# untitled.net
KiCad netlist of a schematic drawn in EAGLE
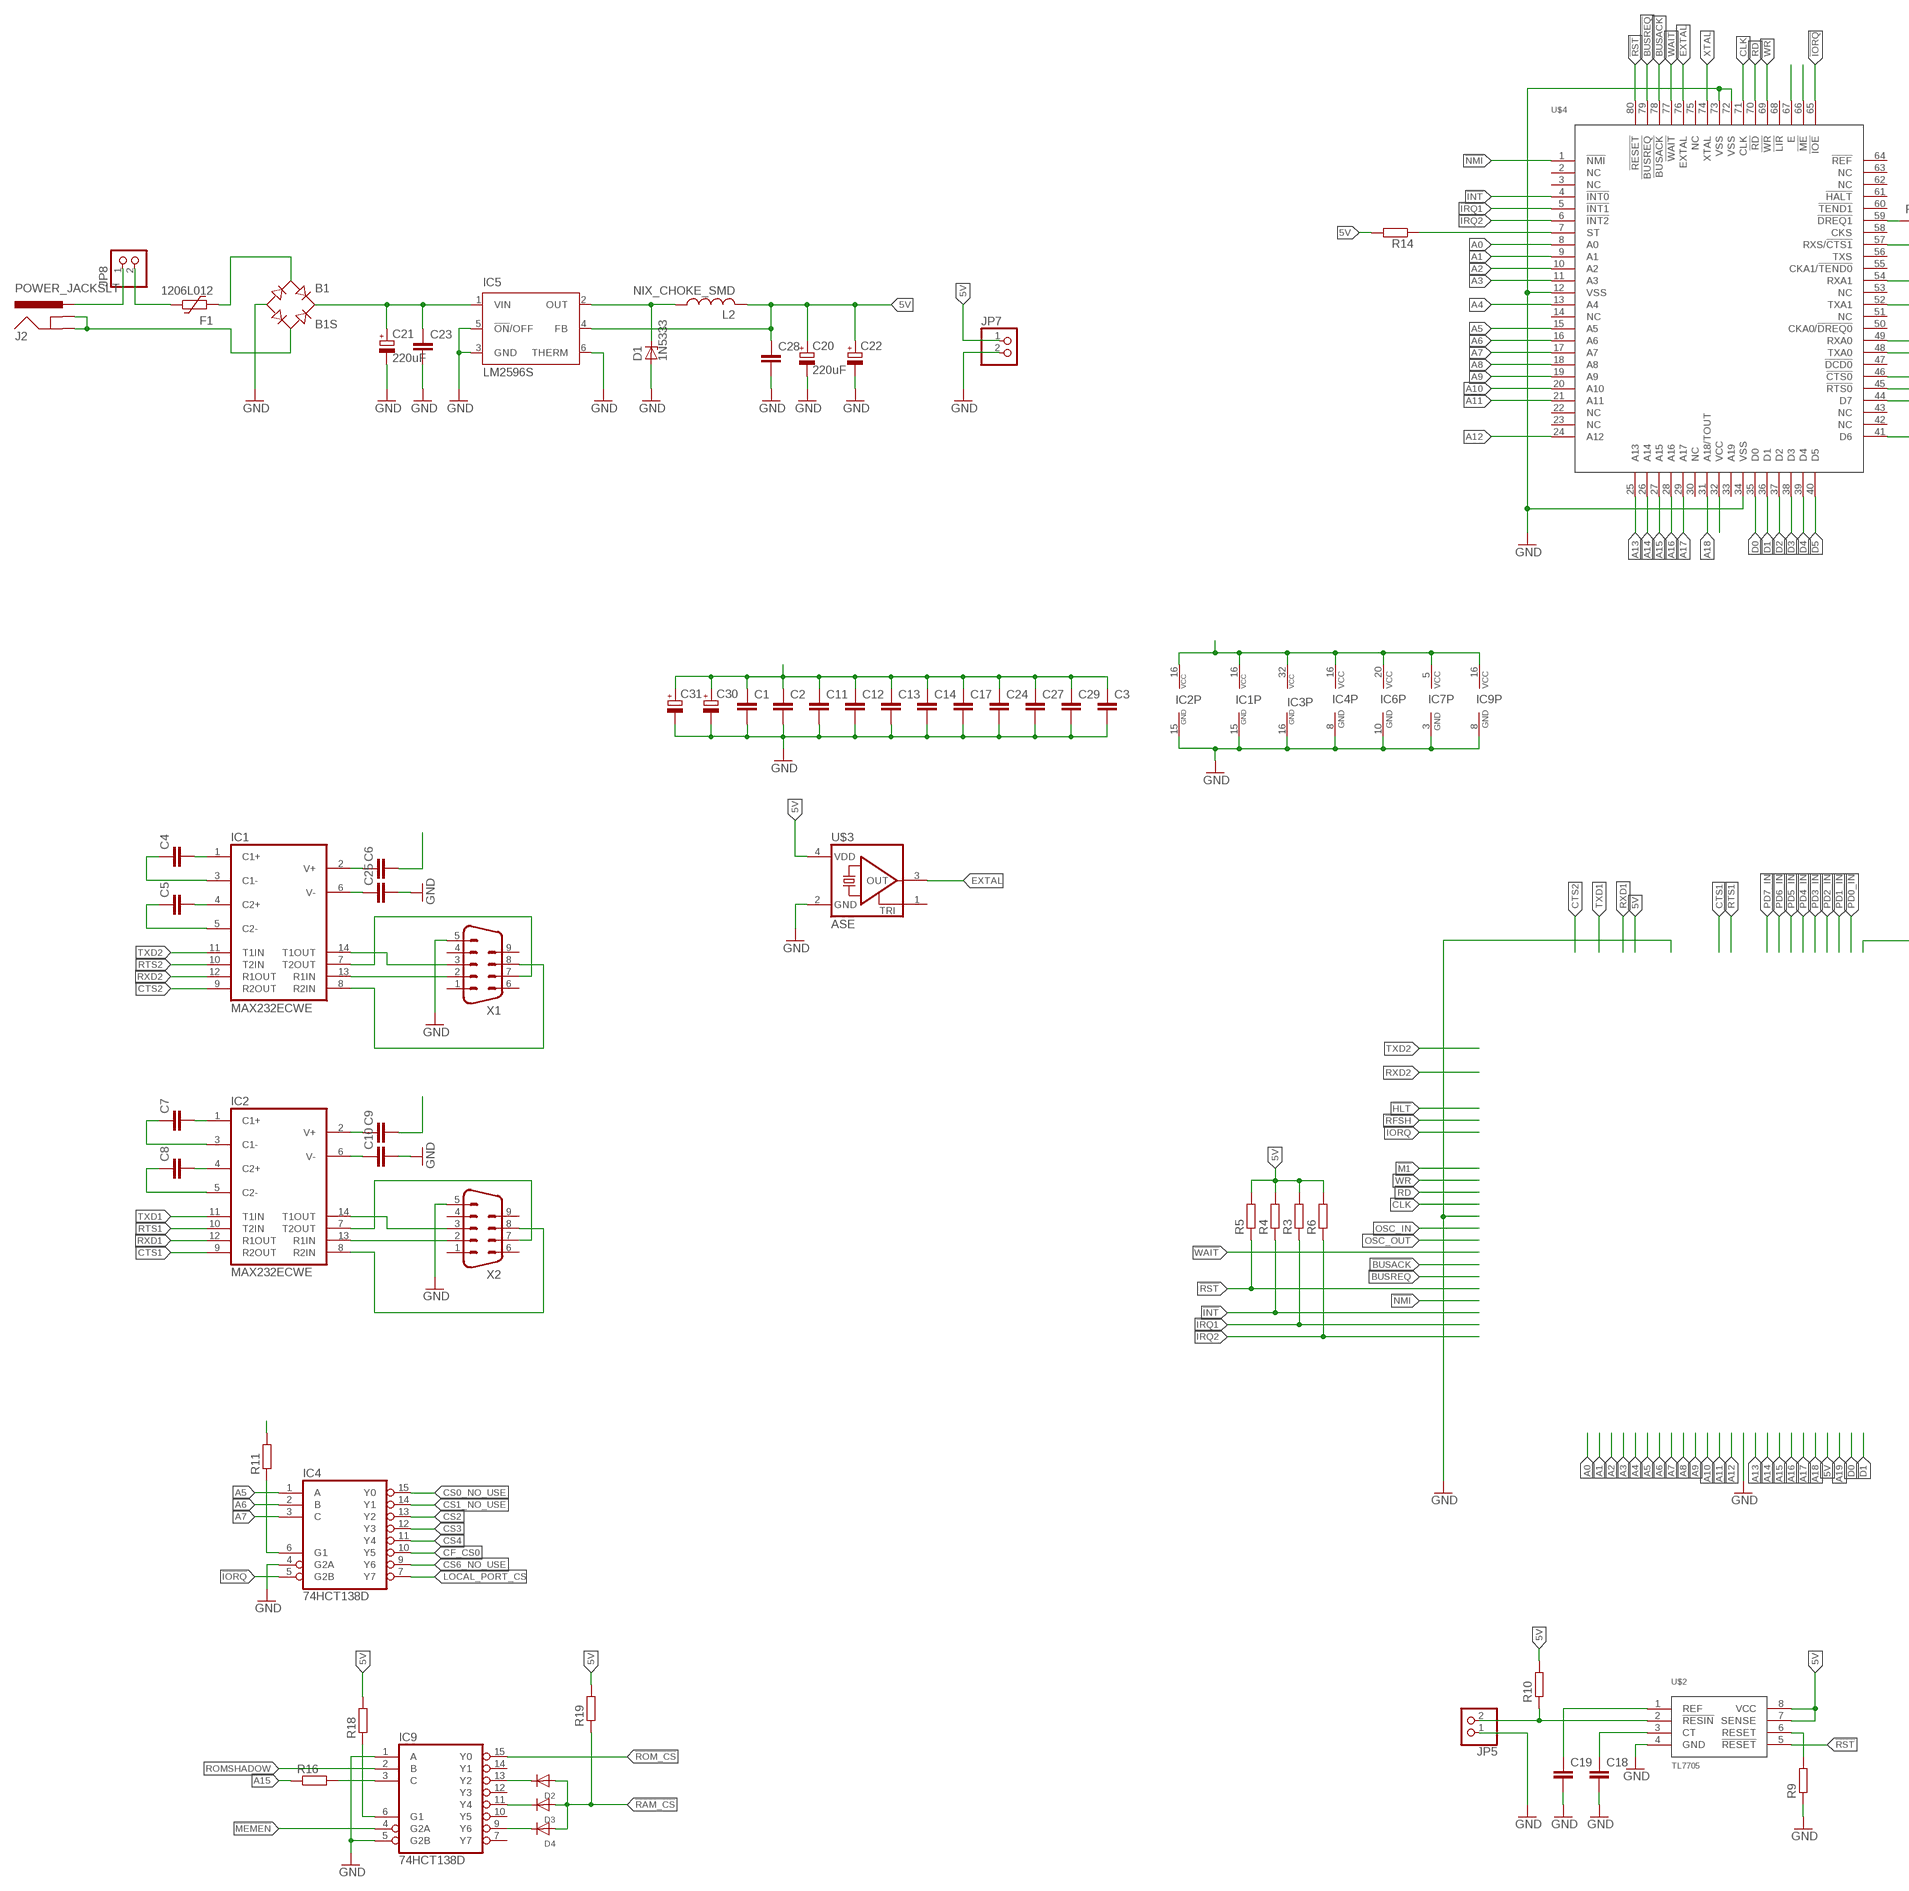
[diagram p0: schematic, sheet 1, part 1 of 2]
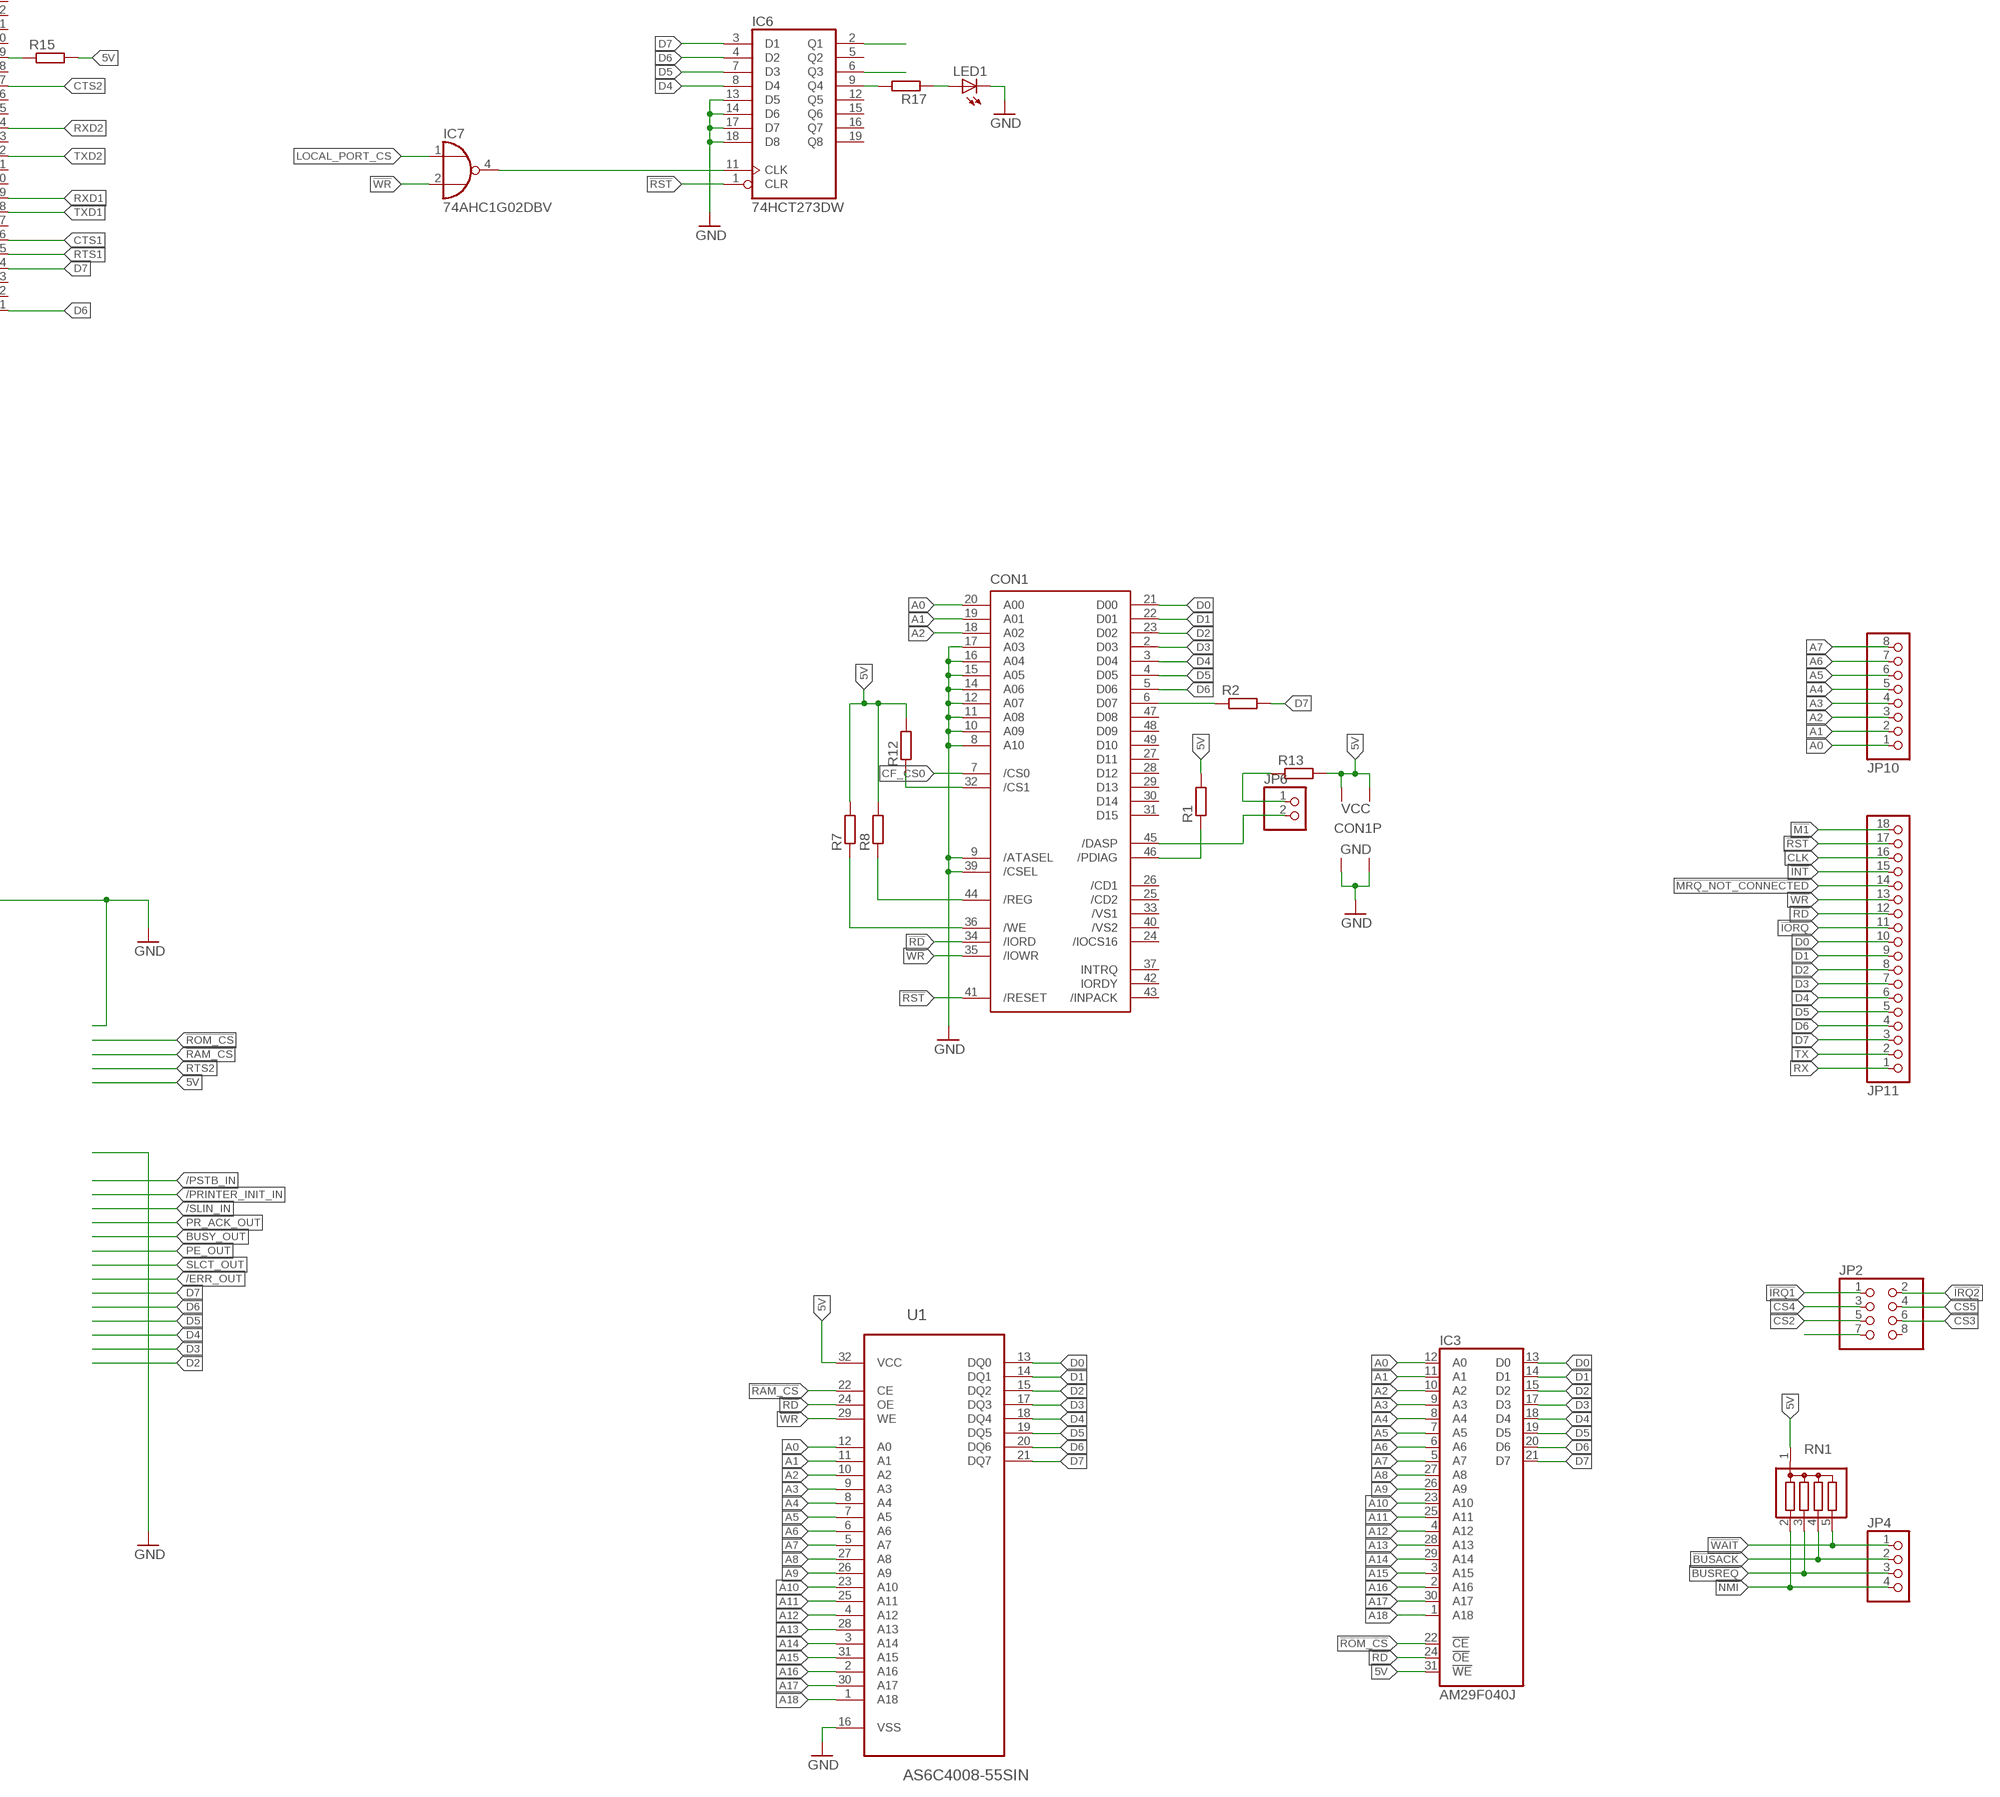
[diagram p1: schematic, sheet 1, part 2 of 2]

(export (version "E")
  (design (tool "Eeschema 10.0.6"))
  (components
    (comp (ref "B1")
      (value "B1S")
      (footprint "eagle-import:MBS")
      (libsource (lib "eagle-import") (part "BS1"))
    )
    (comp (ref "C1")
      (value "C-EUC0603")
      (footprint "eagle-import:C0603")
      (libsource (lib "eagle-import") (part "C-EUC0603"))
    )
    (comp (ref "C2")
      (value "C-EUC0603")
      (footprint "eagle-import:C0603")
      (libsource (lib "eagle-import") (part "C-EUC0603"))
    )
    (comp (ref "C3")
      (value "C-EUC0603")
      (footprint "eagle-import:C0603")
      (libsource (lib "eagle-import") (part "C-EUC0603"))
    )
    (comp (ref "C4")
      (value "C-EUC0603")
      (footprint "eagle-import:C0603")
      (libsource (lib "eagle-import") (part "C-EUC0603"))
    )
    (comp (ref "C5")
      (value "C-EUC0603")
      (footprint "eagle-import:C0603")
      (libsource (lib "eagle-import") (part "C-EUC0603"))
    )
    (comp (ref "C6")
      (value "C-EUC0603")
      (footprint "eagle-import:C0603")
      (libsource (lib "eagle-import") (part "C-EUC0603"))
    )
    (comp (ref "C7")
      (value "C-EUC0603")
      (footprint "eagle-import:C0603")
      (libsource (lib "eagle-import") (part "C-EUC0603"))
    )
    (comp (ref "C8")
      (value "C-EUC0603")
      (footprint "eagle-import:C0603")
      (libsource (lib "eagle-import") (part "C-EUC0603"))
    )
    (comp (ref "C9")
      (value "C-EUC0603")
      (footprint "eagle-import:C0603")
      (libsource (lib "eagle-import") (part "C-EUC0603"))
    )
    (comp (ref "C10")
      (value "C-EUC0603")
      (footprint "eagle-import:C0603")
      (libsource (lib "eagle-import") (part "C-EUC0603"))
    )
    (comp (ref "C11")
      (value "C-EUC0603")
      (footprint "eagle-import:C0603")
      (libsource (lib "eagle-import") (part "C-EUC0603"))
    )
    (comp (ref "C12")
      (value "C-EUC0603")
      (footprint "eagle-import:C0603")
      (libsource (lib "eagle-import") (part "C-EUC0603"))
    )
    (comp (ref "C13")
      (value "C-EUC0402")
      (footprint "eagle-import:C0402")
      (libsource (lib "eagle-import") (part "C-EUC0402"))
    )
    (comp (ref "C14")
      (value "C-EUC0603")
      (footprint "eagle-import:C0603")
      (libsource (lib "eagle-import") (part "C-EUC0603"))
    )
    (comp (ref "C17")
      (value "C-EUC0603")
      (footprint "eagle-import:C0603")
      (libsource (lib "eagle-import") (part "C-EUC0603"))
    )
    (comp (ref "C18")
      (value "C-EUC0603")
      (footprint "eagle-import:C0603")
      (libsource (lib "eagle-import") (part "C-EUC0603"))
    )
    (comp (ref "C19")
      (value "C-EUC0603")
      (footprint "eagle-import:C0603")
      (libsource (lib "eagle-import") (part "C-EUC0603"))
    )
    (comp (ref "C20")
      (value "220uF")
      (footprint "eagle-import:153CLV-0810")
      (libsource (lib "eagle-import") (part "CPOL-EU153CLV-0810"))
    )
    (comp (ref "C21")
      (value "220uF")
      (footprint "eagle-import:153CLV-0810")
      (libsource (lib "eagle-import") (part "CPOL-EU153CLV-0810"))
    )
    (comp (ref "C22")
      (value "CPOL-EUSMCC")
      (footprint "eagle-import:SMC_C")
      (libsource (lib "eagle-import") (part "CPOL-EUSMCC"))
    )
    (comp (ref "C23")
      (value "C-EUC0603")
      (footprint "eagle-import:C0603")
      (libsource (lib "eagle-import") (part "C-EUC0603"))
    )
    (comp (ref "C24")
      (value "C-EUC0603")
      (footprint "eagle-import:C0603")
      (libsource (lib "eagle-import") (part "C-EUC0603"))
    )
    (comp (ref "C25")
      (value "C-EUC0603")
      (footprint "eagle-import:C0603")
      (libsource (lib "eagle-import") (part "C-EUC0603"))
    )
    (comp (ref "C27")
      (value "C-EUC0603")
      (footprint "eagle-import:C0603")
      (libsource (lib "eagle-import") (part "C-EUC0603"))
    )
    (comp (ref "C28")
      (value "C-EUC0603")
      (footprint "eagle-import:C0603")
      (libsource (lib "eagle-import") (part "C-EUC0603"))
    )
    (comp (ref "C29")
      (value "C-EUC0603")
      (footprint "eagle-import:C0603")
      (libsource (lib "eagle-import") (part "C-EUC0603"))
    )
    (comp (ref "C30")
      (value "CPOL-EUSMCB")
      (footprint "eagle-import:SMC_B")
      (libsource (lib "eagle-import") (part "CPOL-EUSMCB"))
    )
    (comp (ref "C31")
      (value "CPOL-EUSMCB")
      (footprint "eagle-import:SMC_B")
      (libsource (lib "eagle-import") (part "CPOL-EUSMCB"))
    )
    (comp (ref "CON1")
      (value "CF-CARD-IDE_MODE")
      (footprint "eagle-import:MI20-50PD-SF")
      (libsource (lib "eagle-import") (part "CF-CARD-IDE_MODE"))
    )
    (comp (ref "D1")
      (value "1N5333")
      (footprint "eagle-import:C1702-15")
      (libsource (lib "eagle-import") (part "1N5333"))
    )
    (comp (ref "D2")
      (value "DIODESOD-323")
      (footprint "eagle-import:SOD-323")
      (libsource (lib "eagle-import") (part "DIODESOD-323"))
    )
    (comp (ref "D3")
      (value "DIODESOD-323")
      (footprint "eagle-import:SOD-323")
      (libsource (lib "eagle-import") (part "DIODESOD-323"))
    )
    (comp (ref "D4")
      (value "DIODESOD-323")
      (footprint "eagle-import:SOD-323")
      (libsource (lib "eagle-import") (part "DIODESOD-323"))
    )
    (comp (ref "F1")
      (value "1206L012")
      (footprint "eagle-import:1206L")
      (fields (field (name "MF") "Littelfuse"))
      (libsource (lib "eagle-import") (part "?1206L012"))
    )
    (comp (ref "IC1")
      (value "MAX232ECWE")
      (footprint "eagle-import:SO16L")
      (fields (field (name "MF") "MAXIM") (field (name "MPN") "MAX232ECWE+"))
      (libsource (lib "eagle-import") (part "MAX232ECWE"))
    )
    (comp (ref "IC2")
      (value "MAX232ECWE")
      (footprint "eagle-import:SO16L")
      (fields (field (name "MF") "MAXIM") (field (name "MPN") "MAX232ECWE+"))
      (libsource (lib "eagle-import") (part "MAX232ECWE"))
    )
    (comp (ref "IC3")
      (value "AM29F040J")
      (footprint "eagle-import:PLCC32R")
      (libsource (lib "eagle-import") (part "AM29F040J"))
    )
    (comp (ref "IC4")
      (value "74HCT138D")
      (footprint "eagle-import:SO16")
      (libsource (lib "eagle-import") (part "74138DHCT"))
    )
    (comp (ref "IC5")
      (value "LM2596S")
      (footprint "eagle-import:TO263-5")
      (fields (field (name "MF") "NATIONAL SEMICONDUCTOR") (field (name "MPN") "LM2596S-ADJ/NOPB"))
      (libsource (lib "eagle-import") (part "LM2596S"))
    )
    (comp (ref "IC6")
      (value "74HCT273DW")
      (footprint "eagle-import:SO20W")
      (libsource (lib "eagle-import") (part "74273DWHCT"))
    )
    (comp (ref "IC7")
      (value "74AHC1G02DBV")
      (footprint "eagle-import:SOT23-5")
      (libsource (lib "eagle-import") (part "741G02DBVAHC"))
    )
    (comp (ref "IC9")
      (value "74HCT138D")
      (footprint "eagle-import:SO16")
      (libsource (lib "eagle-import") (part "74138DHCT"))
    )
    (comp (ref "J2")
      (value "POWER_JACKSLT")
      (footprint "eagle-import:POWER_JACK_SLOT")
      (libsource (lib "eagle-import") (part "POWER_JACKSLT"))
    )
    (comp (ref "JP2")
      (value "PINHD-2X4")
      (footprint "eagle-import:2X04")
      (libsource (lib "eagle-import") (part "PINHD-2X4"))
    )
    (comp (ref "JP4")
      (value "PINHD-1X4")
      (footprint "eagle-import:1X04")
      (libsource (lib "eagle-import") (part "PINHD-1X4"))
    )
    (comp (ref "JP5")
      (value "PINHD-1X2")
      (footprint "eagle-import:1X02")
      (libsource (lib "eagle-import") (part "PINHD-1X2"))
    )
    (comp (ref "JP6")
      (value "PINHD-1X2")
      (footprint "eagle-import:1X02")
      (libsource (lib "eagle-import") (part "PINHD-1X2"))
    )
    (comp (ref "JP7")
      (value "PINHD-1X2")
      (footprint "eagle-import:1X02")
      (libsource (lib "eagle-import") (part "PINHD-1X2"))
    )
    (comp (ref "JP8")
      (value "PINHD-1X2")
      (footprint "eagle-import:1X02")
      (libsource (lib "eagle-import") (part "PINHD-1X2"))
    )
    (comp (ref "JP10")
      (value "PINHD-1X8")
      (footprint "eagle-import:1X08")
      (libsource (lib "eagle-import") (part "PINHD-1X8"))
    )
    (comp (ref "JP11")
      (value "PINHD-1X18")
      (footprint "eagle-import:1X18")
      (libsource (lib "eagle-import") (part "PINHD-1X18"))
    )
    (comp (ref "L2")
      (value "NIX_CHOKE_SMD")
      (footprint "eagle-import:NIX_CHOKE_SMD")
      (libsource (lib "eagle-import") (part "NIX_CHOKE_SMD"))
    )
    (comp (ref "LED1")
      (value "LEDCHIP-LED0603")
      (footprint "eagle-import:CHIP-LED0603")
      (libsource (lib "eagle-import") (part "LEDCHIP-LED0603"))
    )
    (comp (ref "R1")
      (value "R-EU_R0603")
      (footprint "eagle-import:R0603")
      (libsource (lib "eagle-import") (part "R-EU_R0603"))
    )
    (comp (ref "R2")
      (value "R-EU_R0603")
      (footprint "eagle-import:R0603")
      (libsource (lib "eagle-import") (part "R-EU_R0603"))
    )
    (comp (ref "R3")
      (value "R-EU_R0402")
      (footprint "eagle-import:R0402")
      (libsource (lib "eagle-import") (part "R-EU_R0402"))
    )
    (comp (ref "R4")
      (value "R-EU_R0402")
      (footprint "eagle-import:R0402")
      (libsource (lib "eagle-import") (part "R-EU_R0402"))
    )
    (comp (ref "R5")
      (value "R-EU_R1206")
      (footprint "eagle-import:R1206")
      (libsource (lib "eagle-import") (part "R-EU_R1206"))
    )
    (comp (ref "R6")
      (value "R-EU_R0402")
      (footprint "eagle-import:R0402")
      (libsource (lib "eagle-import") (part "R-EU_R0402"))
    )
    (comp (ref "R7")
      (value "R-EU_R0603")
      (footprint "eagle-import:R0603")
      (libsource (lib "eagle-import") (part "R-EU_R0603"))
    )
    (comp (ref "R8")
      (value "R-EU_R0603")
      (footprint "eagle-import:R0603")
      (libsource (lib "eagle-import") (part "R-EU_R0603"))
    )
    (comp (ref "R9")
      (value "R-EU_R0603")
      (footprint "eagle-import:R0603")
      (libsource (lib "eagle-import") (part "R-EU_R0603"))
    )
    (comp (ref "R10")
      (value "R-EU_M1206")
      (footprint "eagle-import:M1206")
      (libsource (lib "eagle-import") (part "R-EU_M1206"))
    )
    (comp (ref "R11")
      (value "R-EU_R0603")
      (footprint "eagle-import:R0603")
      (libsource (lib "eagle-import") (part "R-EU_R0603"))
    )
    (comp (ref "R12")
      (value "R-EU_R0603")
      (footprint "eagle-import:R0603")
      (libsource (lib "eagle-import") (part "R-EU_R0603"))
    )
    (comp (ref "R13")
      (value "R-EU_R0603")
      (footprint "eagle-import:R0603")
      (libsource (lib "eagle-import") (part "R-EU_R0603"))
    )
    (comp (ref "R14")
      (value "R-EU_0204/5")
      (footprint "eagle-import:0204_5")
      (libsource (lib "eagle-import") (part "R-EU_0204/5"))
    )
    (comp (ref "R15")
      (value "R-EU_R0603")
      (footprint "eagle-import:R0603")
      (libsource (lib "eagle-import") (part "R-EU_R0603"))
    )
    (comp (ref "R16")
      (value "R-EU_R0603")
      (footprint "eagle-import:R0603")
      (libsource (lib "eagle-import") (part "R-EU_R0603"))
    )
    (comp (ref "R17")
      (value "R-EU_R0603")
      (footprint "eagle-import:R0603")
      (libsource (lib "eagle-import") (part "R-EU_R0603"))
    )
    (comp (ref "R18")
      (value "R-EU_R0603")
      (footprint "eagle-import:R0603")
      (libsource (lib "eagle-import") (part "R-EU_R0603"))
    )
    (comp (ref "R19")
      (value "R-EU_R0603")
      (footprint "eagle-import:R0603")
      (libsource (lib "eagle-import") (part "R-EU_R0603"))
    )
    (comp (ref "RN1")
      (value "G04R")
      (footprint "eagle-import:SIL5")
      (libsource (lib "eagle-import") (part "G04R"))
    )
    (comp (ref "U$2")
      (value "TL7705")
      (footprint "eagle-import:SOIC8")
      (libsource (lib "eagle-import") (part "TL7705"))
    )
    (comp (ref "U$3")
      (value "ASE")
      (footprint "eagle-import:ASE")
      (libsource (lib "eagle-import") (part "ASE"))
    )
    (comp (ref "U$4")
      (value "HD64180QFP80_")
      (footprint "eagle-import:QFP80")
      (libsource (lib "eagle-import") (part "HD64180QFP80_"))
    )
    (comp (ref "U1")
      (value "AS6C4008-55SIN")
      (footprint "eagle-import:SOIC127P1407X299-32N")
      (libsource (lib "eagle-import") (part "AS6C4008-55SIN"))
    )
    (comp (ref "X1")
      (value "M09HP")
      (footprint "eagle-import:M09HP")
      (libsource (lib "eagle-import") (part "M09HP"))
    )
    (comp (ref "X2")
      (value "M09HP")
      (footprint "eagle-import:M09HP")
      (libsource (lib "eagle-import") (part "M09HP"))
    )
  )
  (nets
    (net (code "1") (name "/E") (class "Default")
      (node (ref "JP2") (pin "7") (pinfunction "7_7") (pintype "passive"))
      (node (ref "U$4") (pin "67") (pinfunction "E_67") (pintype "bidirectional"))
    )
    (net (code "2") (name "/~{BUSACK}") (class "Default")
      (node (ref "JP4") (pin "2") (pinfunction "2_2") (pintype "passive"))
      (node (ref "RN1") (pin "4") (pinfunction "4_4") (pintype "passive"))
      (node (ref "U$4") (pin "78") (pinfunction "~{BUSACK}_78") (pintype "bidirectional"))
    )
    (net (code "3") (name "/~{BUSREQ}") (class "Default")
      (node (ref "JP4") (pin "3") (pinfunction "3_3") (pintype "passive"))
      (node (ref "RN1") (pin "3") (pinfunction "3_3") (pintype "passive"))
      (node (ref "U$4") (pin "79") (pinfunction "~{BUSREQ}_79") (pintype "bidirectional"))
    )
    (net (code "5") (name "/~{INT}") (class "Default")
      (node (ref "JP11") (pin "15") (pinfunction "15_15") (pintype "passive"))
      (node (ref "R4") (pin "1") (pinfunction "1_1") (pintype "passive"))
      (node (ref "U$4") (pin "4") (pinfunction "~{INT0}_4") (pintype "bidirectional"))
    )
    (net (code "6") (name "/~{IORQ}") (class "Default")
      (node (ref "IC4") (pin "5") (pinfunction "G2B_5") (pintype "input"))
      (node (ref "JP11") (pin "11") (pinfunction "11_11") (pintype "passive"))
      (node (ref "U$4") (pin "65") (pinfunction "~{IOE}_65") (pintype "bidirectional"))
    )
    (net (code "7") (name "/~{IRQ1}") (class "Default")
      (node (ref "JP2") (pin "1") (pinfunction "1_1") (pintype "passive"))
      (node (ref "R3") (pin "1") (pinfunction "1_1") (pintype "passive"))
      (node (ref "U$4") (pin "5") (pinfunction "~{INT1}_5") (pintype "bidirectional"))
    )
    (net (code "8") (name "/~{IRQ2}") (class "Default")
      (node (ref "JP2") (pin "2") (pinfunction "2_2") (pintype "passive"))
      (node (ref "R6") (pin "1") (pinfunction "1_1") (pintype "passive"))
      (node (ref "U$4") (pin "6") (pinfunction "~{INT2}_6") (pintype "bidirectional"))
    )
    (net (code "9") (name "/~{M1}") (class "Default")
      (node (ref "JP11") (pin "18") (pinfunction "18_18") (pintype "passive"))
    )
    (net (code "10") (name "/~{MEMEN}") (class "Default")
      (node (ref "IC9") (pin "4") (pinfunction "G2A_4") (pintype "input"))
      (node (ref "U$4") (pin "66") (pinfunction "~{ME}_66") (pintype "bidirectional"))
    )
    (net (code "11") (name "/~{MRQ_NOT_CONNECTED}") (class "Default")
      (node (ref "JP11") (pin "14") (pinfunction "14_14") (pintype "passive"))
    )
    (net (code "12") (name "/~{NMI}") (class "Default")
      (node (ref "JP4") (pin "4") (pinfunction "4_4") (pintype "passive"))
      (node (ref "RN1") (pin "2") (pinfunction "2_2") (pintype "passive"))
      (node (ref "U$4") (pin "1") (pinfunction "~{NMI}_1") (pintype "bidirectional"))
    )
    (net (code "13") (name "/~{RAM_CS}") (class "Default")
      (node (ref "D2") (pin "A") (pinfunction "A_A") (pintype "passive"))
      (node (ref "D3") (pin "A") (pinfunction "A_A") (pintype "passive"))
      (node (ref "D4") (pin "A") (pinfunction "A_A") (pintype "passive"))
      (node (ref "R19") (pin "1") (pinfunction "1_1") (pintype "passive"))
      (node (ref "U1") (pin "22") (pinfunction "CE_22") (pintype "input"))
    )
    (net (code "14") (name "/~{RD}") (class "Default")
      (node (ref "CON1") (pin "34") (pinfunction "/IORD_34") (pintype "input"))
      (node (ref "IC3") (pin "24") (pinfunction "~{OE}_24") (pintype "input"))
      (node (ref "JP11") (pin "12") (pinfunction "12_12") (pintype "passive"))
      (node (ref "U$4") (pin "70") (pinfunction "~{RD}_70") (pintype "bidirectional"))
      (node (ref "U1") (pin "24") (pinfunction "OE_24") (pintype "input"))
    )
    (net (code "16") (name "/~{ROM_CS}") (class "Default")
      (node (ref "IC3") (pin "22") (pinfunction "~{CE}_22") (pintype "input"))
      (node (ref "IC9") (pin "15") (pinfunction "Y0_15") (pintype "output"))
    )
    (net (code "17") (name "/~{RST}") (class "Default")
      (node (ref "CON1") (pin "41") (pinfunction "/RESET_41") (pintype "input"))
      (node (ref "IC6") (pin "1") (pinfunction "CLR_1") (pintype "input"))
      (node (ref "JP11") (pin "17") (pinfunction "17_17") (pintype "passive"))
      (node (ref "R5") (pin "1") (pinfunction "1_1") (pintype "passive"))
      (node (ref "U$2") (pin "5") (pinfunction "~{RESET}_5") (pintype "bidirectional"))
      (node (ref "U$4") (pin "80") (pinfunction "~{RESET}_80") (pintype "bidirectional"))
    )
    (net (code "18") (name "/~{WAIT}") (class "Default")
      (node (ref "JP4") (pin "1") (pinfunction "1_1") (pintype "passive"))
      (node (ref "RN1") (pin "5") (pinfunction "5_5") (pintype "passive"))
      (node (ref "U$4") (pin "77") (pinfunction "~{WAIT}_77") (pintype "bidirectional"))
    )
    (net (code "19") (name "/~{WR}") (class "Default")
      (node (ref "CON1") (pin "35") (pinfunction "/IOWR_35") (pintype "input"))
      (node (ref "IC7") (pin "2") (pinfunction "I1_2") (pintype "input"))
      (node (ref "JP11") (pin "13") (pinfunction "13_13") (pintype "passive"))
      (node (ref "U$4") (pin "69") (pinfunction "~{WR}_69") (pintype "bidirectional"))
      (node (ref "U1") (pin "29") (pinfunction "WE_29") (pintype "input"))
    )
    (net (code "20") (name "5V") (class "Default")
      (node (ref "C1") (pin "1") (pinfunction "1_1") (pintype "passive"))
      (node (ref "C11") (pin "1") (pinfunction "1_1") (pintype "passive"))
      (node (ref "C12") (pin "1") (pinfunction "1_1") (pintype "passive"))
      (node (ref "C13") (pin "1") (pinfunction "1_1") (pintype "passive"))
      (node (ref "C14") (pin "1") (pinfunction "1_1") (pintype "passive"))
      (node (ref "C17") (pin "1") (pinfunction "1_1") (pintype "passive"))
      (node (ref "C2") (pin "1") (pinfunction "1_1") (pintype "passive"))
      (node (ref "C20") (pin "+") (pinfunction "+_+") (pintype "passive"))
      (node (ref "C22") (pin "+") (pinfunction "+_+") (pintype "passive"))
      (node (ref "C24") (pin "1") (pinfunction "1_1") (pintype "passive"))
      (node (ref "C27") (pin "1") (pinfunction "1_1") (pintype "passive"))
      (node (ref "C28") (pin "1") (pinfunction "1_1") (pintype "passive"))
      (node (ref "C29") (pin "1") (pinfunction "1_1") (pintype "passive"))
      (node (ref "C3") (pin "1") (pinfunction "1_1") (pintype "passive"))
      (node (ref "C30") (pin "+") (pinfunction "+_+") (pintype "passive"))
      (node (ref "C31") (pin "+") (pinfunction "+_+") (pintype "passive"))
      (node (ref "C6") (pin "2") (pinfunction "2_2") (pintype "passive"))
      (node (ref "C9") (pin "2") (pinfunction "2_2") (pintype "passive"))
      (node (ref "CON1") (pin "13") (pinfunction "VCC2_13") (pintype "power_in"))
      (node (ref "CON1") (pin "38") (pinfunction "VCC1_38") (pintype "power_in"))
      (node (ref "IC1") (pin "16") (pinfunction "VCC_16") (pintype "power_in"))
      (node (ref "IC2") (pin "16") (pinfunction "VCC_16") (pintype "power_in"))
      (node (ref "IC3") (pin "31") (pinfunction "~{WE}_31") (pintype "input"))
      (node (ref "IC3") (pin "32") (pinfunction "VCC_32") (pintype "power_in"))
      (node (ref "IC4") (pin "16") (pinfunction "VCC_16") (pintype "power_in"))
      (node (ref "IC5") (pin "4") (pinfunction "FB_4") (pintype "input"))
      (node (ref "IC6") (pin "20") (pinfunction "VCC_20") (pintype "power_in"))
      (node (ref "IC7") (pin "5") (pinfunction "VCC_5") (pintype "power_in"))
      (node (ref "IC9") (pin "16") (pinfunction "VCC_16") (pintype "power_in"))
      (node (ref "JP7") (pin "1") (pinfunction "1_1") (pintype "passive"))
      (node (ref "L2") (pin "P$2") (pinfunction "2_P$2") (pintype "passive"))
      (node (ref "R1") (pin "2") (pinfunction "2_2") (pintype "passive"))
      (node (ref "R10") (pin "2") (pinfunction "2_2") (pintype "passive"))
      (node (ref "R11") (pin "2") (pinfunction "2_2") (pintype "passive"))
      (node (ref "R12") (pin "2") (pinfunction "2_2") (pintype "passive"))
      (node (ref "R13") (pin "2") (pinfunction "2_2") (pintype "passive"))
      (node (ref "R14") (pin "2") (pinfunction "2_2") (pintype "passive"))
      (node (ref "R15") (pin "2") (pinfunction "2_2") (pintype "passive"))
      (node (ref "R18") (pin "2") (pinfunction "2_2") (pintype "passive"))
      (node (ref "R19") (pin "2") (pinfunction "2_2") (pintype "passive"))
      (node (ref "R3") (pin "2") (pinfunction "2_2") (pintype "passive"))
      (node (ref "R4") (pin "2") (pinfunction "2_2") (pintype "passive"))
      (node (ref "R5") (pin "2") (pinfunction "2_2") (pintype "passive"))
      (node (ref "R6") (pin "2") (pinfunction "2_2") (pintype "passive"))
      (node (ref "R7") (pin "2") (pinfunction "2_2") (pintype "passive"))
      (node (ref "R8") (pin "2") (pinfunction "2_2") (pintype "passive"))
      (node (ref "RN1") (pin "1") (pinfunction "1_1") (pintype "passive"))
      (node (ref "U$2") (pin "7") (pinfunction "SENSE_7") (pintype "bidirectional"))
      (node (ref "U$2") (pin "8") (pinfunction "VCC_8") (pintype "bidirectional"))
      (node (ref "U$3") (pin "4") (pinfunction "VDD_4") (pintype "power_in"))
      (node (ref "U$4") (pin "32") (pinfunction "VCC_32") (pintype "bidirectional"))
      (node (ref "U1") (pin "32") (pinfunction "VCC_32") (pintype "power_in"))
    )
    (net (code "21") (name "A0") (class "Default")
      (node (ref "CON1") (pin "20") (pinfunction "A00_20") (pintype "input"))
      (node (ref "IC3") (pin "12") (pinfunction "A0_12") (pintype "input"))
      (node (ref "JP10") (pin "1") (pinfunction "1_1") (pintype "passive"))
      (node (ref "U$4") (pin "8") (pinfunction "A0_8") (pintype "bidirectional"))
      (node (ref "U1") (pin "12") (pinfunction "A0_12") (pintype "input"))
    )
    (net (code "22") (name "A1") (class "Default")
      (node (ref "CON1") (pin "19") (pinfunction "A01_19") (pintype "input"))
      (node (ref "IC3") (pin "11") (pinfunction "A1_11") (pintype "input"))
      (node (ref "JP10") (pin "2") (pinfunction "2_2") (pintype "passive"))
      (node (ref "U$4") (pin "9") (pinfunction "A1_9") (pintype "bidirectional"))
      (node (ref "U1") (pin "11") (pinfunction "A1_11") (pintype "input"))
    )
    (net (code "23") (name "A2") (class "Default")
      (node (ref "CON1") (pin "18") (pinfunction "A02_18") (pintype "input"))
      (node (ref "IC3") (pin "10") (pinfunction "A2_10") (pintype "input"))
      (node (ref "JP10") (pin "3") (pinfunction "3_3") (pintype "passive"))
      (node (ref "U$4") (pin "10") (pinfunction "A2_10") (pintype "bidirectional"))
      (node (ref "U1") (pin "10") (pinfunction "A2_10") (pintype "input"))
    )
    (net (code "24") (name "A3") (class "Default")
      (node (ref "IC3") (pin "9") (pinfunction "A3_9") (pintype "input"))
      (node (ref "JP10") (pin "4") (pinfunction "4_4") (pintype "passive"))
      (node (ref "U$4") (pin "11") (pinfunction "A3_11") (pintype "bidirectional"))
      (node (ref "U1") (pin "9") (pinfunction "A3_9") (pintype "input"))
    )
    (net (code "25") (name "A4") (class "Default")
      (node (ref "IC3") (pin "8") (pinfunction "A4_8") (pintype "input"))
      (node (ref "JP10") (pin "5") (pinfunction "5_5") (pintype "passive"))
      (node (ref "U$4") (pin "13") (pinfunction "A4_13") (pintype "bidirectional"))
      (node (ref "U1") (pin "8") (pinfunction "A4_8") (pintype "input"))
    )
    (net (code "26") (name "A5") (class "Default")
      (node (ref "IC3") (pin "7") (pinfunction "A5_7") (pintype "input"))
      (node (ref "IC4") (pin "1") (pinfunction "A_1") (pintype "input"))
      (node (ref "JP10") (pin "6") (pinfunction "6_6") (pintype "passive"))
      (node (ref "U$4") (pin "15") (pinfunction "A5_15") (pintype "bidirectional"))
      (node (ref "U1") (pin "7") (pinfunction "A5_7") (pintype "input"))
    )
    (net (code "27") (name "A6") (class "Default")
      (node (ref "IC3") (pin "6") (pinfunction "A6_6") (pintype "input"))
      (node (ref "IC4") (pin "2") (pinfunction "B_2") (pintype "input"))
      (node (ref "JP10") (pin "7") (pinfunction "7_7") (pintype "passive"))
      (node (ref "U$4") (pin "16") (pinfunction "A6_16") (pintype "bidirectional"))
      (node (ref "U1") (pin "6") (pinfunction "A6_6") (pintype "input"))
    )
    (net (code "28") (name "A7") (class "Default")
      (node (ref "IC3") (pin "5") (pinfunction "A7_5") (pintype "input"))
      (node (ref "IC4") (pin "3") (pinfunction "C_3") (pintype "input"))
      (node (ref "JP10") (pin "8") (pinfunction "8_8") (pintype "passive"))
      (node (ref "U$4") (pin "17") (pinfunction "A7_17") (pintype "bidirectional"))
      (node (ref "U1") (pin "5") (pinfunction "A7_5") (pintype "input"))
    )
    (net (code "29") (name "A8") (class "Default")
      (node (ref "IC3") (pin "27") (pinfunction "A8_27") (pintype "input"))
      (node (ref "U$4") (pin "18") (pinfunction "A8_18") (pintype "bidirectional"))
      (node (ref "U1") (pin "27") (pinfunction "A8_27") (pintype "input"))
    )
    (net (code "30") (name "A9") (class "Default")
      (node (ref "IC3") (pin "26") (pinfunction "A9_26") (pintype "input"))
      (node (ref "U$4") (pin "19") (pinfunction "A9_19") (pintype "bidirectional"))
      (node (ref "U1") (pin "26") (pinfunction "A9_26") (pintype "input"))
    )
    (net (code "31") (name "A10") (class "Default")
      (node (ref "IC3") (pin "23") (pinfunction "A10_23") (pintype "input"))
      (node (ref "U$4") (pin "20") (pinfunction "A10_20") (pintype "bidirectional"))
      (node (ref "U1") (pin "23") (pinfunction "A10_23") (pintype "input"))
    )
    (net (code "32") (name "A11") (class "Default")
      (node (ref "IC3") (pin "25") (pinfunction "A11_25") (pintype "input"))
      (node (ref "U$4") (pin "21") (pinfunction "A11_21") (pintype "bidirectional"))
      (node (ref "U1") (pin "25") (pinfunction "A11_25") (pintype "input"))
    )
    (net (code "33") (name "A12") (class "Default")
      (node (ref "IC3") (pin "4") (pinfunction "A12_4") (pintype "input"))
      (node (ref "U$4") (pin "24") (pinfunction "A12_24") (pintype "bidirectional"))
      (node (ref "U1") (pin "4") (pinfunction "A12_4") (pintype "input"))
    )
    (net (code "34") (name "A13") (class "Default")
      (node (ref "IC3") (pin "28") (pinfunction "A13_28") (pintype "input"))
      (node (ref "U$4") (pin "25") (pinfunction "A13_25") (pintype "bidirectional"))
      (node (ref "U1") (pin "28") (pinfunction "A13_28") (pintype "input"))
    )
    (net (code "35") (name "A14") (class "Default")
      (node (ref "IC3") (pin "29") (pinfunction "A14_29") (pintype "input"))
      (node (ref "U$4") (pin "26") (pinfunction "A14_26") (pintype "bidirectional"))
      (node (ref "U1") (pin "3") (pinfunction "A14_3") (pintype "input"))
    )
    (net (code "36") (name "A15") (class "Default")
      (node (ref "IC3") (pin "3") (pinfunction "A15_3") (pintype "input"))
      (node (ref "R16") (pin "1") (pinfunction "1_1") (pintype "passive"))
      (node (ref "U$4") (pin "27") (pinfunction "A15_27") (pintype "bidirectional"))
      (node (ref "U1") (pin "31") (pinfunction "A15_31") (pintype "input"))
    )
    (net (code "37") (name "A16") (class "Default")
      (node (ref "IC3") (pin "2") (pinfunction "A16_2") (pintype "input"))
      (node (ref "U$4") (pin "28") (pinfunction "A16_28") (pintype "bidirectional"))
      (node (ref "U1") (pin "2") (pinfunction "A16_2") (pintype "input"))
    )
    (net (code "38") (name "A17") (class "Default")
      (node (ref "IC3") (pin "30") (pinfunction "A17_30") (pintype "input"))
      (node (ref "U$4") (pin "29") (pinfunction "A17_29") (pintype "bidirectional"))
      (node (ref "U1") (pin "30") (pinfunction "A17_30") (pintype "input"))
    )
    (net (code "39") (name "A18") (class "Default")
      (node (ref "IC3") (pin "1") (pinfunction "A18_1") (pintype "input"))
      (node (ref "U$4") (pin "31") (pinfunction "A18/TOUT_31") (pintype "bidirectional"))
      (node (ref "U1") (pin "1") (pinfunction "A18_1") (pintype "input"))
    )
    (net (code "42") (name "CF_CS0") (class "Default")
      (node (ref "CON1") (pin "7") (pinfunction "/CS0_7") (pintype "input"))
      (node (ref "IC4") (pin "10") (pinfunction "Y5_10") (pintype "output"))
    )
    (net (code "43") (name "CLK") (class "Default")
      (node (ref "JP11") (pin "16") (pinfunction "16_16") (pintype "passive"))
      (node (ref "U$4") (pin "71") (pinfunction "CLK_71") (pintype "bidirectional"))
    )
    (net (code "44") (name "CS0_NO_USE") (class "Default")
      (node (ref "IC4") (pin "15") (pinfunction "Y0_15") (pintype "output"))
    )
    (net (code "45") (name "CS1_NO_USE") (class "Default")
      (node (ref "IC4") (pin "14") (pinfunction "Y1_14") (pintype "output"))
    )
    (net (code "46") (name "CS2") (class "Default")
      (node (ref "IC4") (pin "13") (pinfunction "Y2_13") (pintype "output"))
      (node (ref "JP2") (pin "5") (pinfunction "5_5") (pintype "passive"))
    )
    (net (code "47") (name "CS3") (class "Default")
      (node (ref "IC4") (pin "12") (pinfunction "Y3_12") (pintype "output"))
      (node (ref "JP2") (pin "6") (pinfunction "6_6") (pintype "passive"))
    )
    (net (code "48") (name "CS4") (class "Default")
      (node (ref "IC4") (pin "11") (pinfunction "Y4_11") (pintype "output"))
      (node (ref "JP2") (pin "3") (pinfunction "3_3") (pintype "passive"))
    )
    (net (code "49") (name "CS5") (class "Default")
      (node (ref "JP2") (pin "4") (pinfunction "4_4") (pintype "passive"))
    )
    (net (code "50") (name "CS6_NO_USE") (class "Default")
      (node (ref "IC4") (pin "9") (pinfunction "Y6_9") (pintype "output"))
    )
    (net (code "51") (name "CTS1") (class "Default")
      (node (ref "IC2") (pin "9") (pinfunction "R2OUT_9") (pintype "output"))
      (node (ref "U$4") (pin "46") (pinfunction "~{CTS0}_46") (pintype "bidirectional"))
    )
    (net (code "52") (name "CTS2") (class "Default")
      (node (ref "IC1") (pin "9") (pinfunction "R2OUT_9") (pintype "output"))
      (node (ref "U$4") (pin "57") (pinfunction "RXS/~{CTS1}_57") (pintype "bidirectional"))
    )
    (net (code "53") (name "D0") (class "Default")
      (node (ref "CON1") (pin "21") (pinfunction "D00_21") (pintype "bidirectional"))
      (node (ref "IC3") (pin "13") (pinfunction "D0_13") (pintype "tri_state"))
      (node (ref "JP11") (pin "10") (pinfunction "10_10") (pintype "passive"))
      (node (ref "U$4") (pin "35") (pinfunction "D0_35") (pintype "bidirectional"))
      (node (ref "U1") (pin "13") (pinfunction "DQ0_13") (pintype "output"))
    )
    (net (code "54") (name "D1") (class "Default")
      (node (ref "CON1") (pin "22") (pinfunction "D01_22") (pintype "bidirectional"))
      (node (ref "IC3") (pin "14") (pinfunction "D1_14") (pintype "tri_state"))
      (node (ref "JP11") (pin "9") (pinfunction "9_9") (pintype "passive"))
      (node (ref "U$4") (pin "36") (pinfunction "D1_36") (pintype "bidirectional"))
      (node (ref "U1") (pin "14") (pinfunction "DQ1_14") (pintype "output"))
    )
    (net (code "55") (name "D2") (class "Default")
      (node (ref "CON1") (pin "23") (pinfunction "D02_23") (pintype "bidirectional"))
      (node (ref "IC3") (pin "15") (pinfunction "D2_15") (pintype "tri_state"))
      (node (ref "JP11") (pin "8") (pinfunction "8_8") (pintype "passive"))
      (node (ref "U$4") (pin "37") (pinfunction "D2_37") (pintype "bidirectional"))
      (node (ref "U1") (pin "15") (pinfunction "DQ2_15") (pintype "output"))
    )
    (net (code "56") (name "D3") (class "Default")
      (node (ref "CON1") (pin "2") (pinfunction "D03_2") (pintype "bidirectional"))
      (node (ref "IC3") (pin "17") (pinfunction "D3_17") (pintype "tri_state"))
      (node (ref "JP11") (pin "7") (pinfunction "7_7") (pintype "passive"))
      (node (ref "U$4") (pin "38") (pinfunction "D3_38") (pintype "bidirectional"))
      (node (ref "U1") (pin "17") (pinfunction "DQ3_17") (pintype "output"))
    )
    (net (code "57") (name "D4") (class "Default")
      (node (ref "CON1") (pin "3") (pinfunction "D04_3") (pintype "bidirectional"))
      (node (ref "IC3") (pin "18") (pinfunction "D4_18") (pintype "tri_state"))
      (node (ref "IC6") (pin "8") (pinfunction "D4_8") (pintype "input"))
      (node (ref "JP11") (pin "6") (pinfunction "6_6") (pintype "passive"))
      (node (ref "U$4") (pin "39") (pinfunction "D4_39") (pintype "bidirectional"))
      (node (ref "U1") (pin "18") (pinfunction "DQ4_18") (pintype "output"))
    )
    (net (code "58") (name "D5") (class "Default")
      (node (ref "CON1") (pin "4") (pinfunction "D05_4") (pintype "bidirectional"))
      (node (ref "IC3") (pin "19") (pinfunction "D5_19") (pintype "tri_state"))
      (node (ref "IC6") (pin "7") (pinfunction "D3_7") (pintype "input"))
      (node (ref "JP11") (pin "5") (pinfunction "5_5") (pintype "passive"))
      (node (ref "U$4") (pin "40") (pinfunction "D5_40") (pintype "bidirectional"))
      (node (ref "U1") (pin "19") (pinfunction "DQ5_19") (pintype "output"))
    )
    (net (code "59") (name "D6") (class "Default")
      (node (ref "CON1") (pin "5") (pinfunction "D06_5") (pintype "bidirectional"))
      (node (ref "IC3") (pin "20") (pinfunction "D6_20") (pintype "tri_state"))
      (node (ref "IC6") (pin "4") (pinfunction "D2_4") (pintype "input"))
      (node (ref "JP11") (pin "4") (pinfunction "4_4") (pintype "passive"))
      (node (ref "U$4") (pin "41") (pinfunction "D6_41") (pintype "bidirectional"))
      (node (ref "U1") (pin "20") (pinfunction "DQ6_20") (pintype "output"))
    )
    (net (code "60") (name "D7") (class "Default")
      (node (ref "IC3") (pin "21") (pinfunction "D7_21") (pintype "tri_state"))
      (node (ref "IC6") (pin "3") (pinfunction "D1_3") (pintype "input"))
      (node (ref "JP11") (pin "3") (pinfunction "3_3") (pintype "passive"))
      (node (ref "R2") (pin "2") (pinfunction "2_2") (pintype "passive"))
      (node (ref "U$4") (pin "44") (pinfunction "D7_44") (pintype "bidirectional"))
      (node (ref "U1") (pin "21") (pinfunction "DQ7_21") (pintype "output"))
    )
    (net (code "61") (name "EXTAL") (class "Default")
      (node (ref "U$3") (pin "3") (pinfunction "OUT_3") (pintype "output"))
      (node (ref "U$4") (pin "76") (pinfunction "EXTAL_76") (pintype "bidirectional"))
    )
    (net (code "62") (name "GND") (class "Default")
      (node (ref "B1") (pin "-") (pinfunction "-_-") (pintype "passive"))
      (node (ref "C1") (pin "2") (pinfunction "2_2") (pintype "passive"))
      (node (ref "C10") (pin "2") (pinfunction "2_2") (pintype "passive"))
      (node (ref "C11") (pin "2") (pinfunction "2_2") (pintype "passive"))
      (node (ref "C12") (pin "2") (pinfunction "2_2") (pintype "passive"))
      (node (ref "C13") (pin "2") (pinfunction "2_2") (pintype "passive"))
      (node (ref "C14") (pin "2") (pinfunction "2_2") (pintype "passive"))
      (node (ref "C17") (pin "2") (pinfunction "2_2") (pintype "passive"))
      (node (ref "C18") (pin "2") (pinfunction "2_2") (pintype "passive"))
      (node (ref "C19") (pin "2") (pinfunction "2_2") (pintype "passive"))
      (node (ref "C2") (pin "2") (pinfunction "2_2") (pintype "passive"))
      (node (ref "C20") (pin "-") (pinfunction "-_-") (pintype "passive"))
      (node (ref "C21") (pin "-") (pinfunction "-_-") (pintype "passive"))
      (node (ref "C22") (pin "-") (pinfunction "-_-") (pintype "passive"))
      (node (ref "C23") (pin "2") (pinfunction "2_2") (pintype "passive"))
      (node (ref "C24") (pin "2") (pinfunction "2_2") (pintype "passive"))
      (node (ref "C25") (pin "2") (pinfunction "2_2") (pintype "passive"))
      (node (ref "C27") (pin "2") (pinfunction "2_2") (pintype "passive"))
      (node (ref "C28") (pin "2") (pinfunction "2_2") (pintype "passive"))
      (node (ref "C29") (pin "2") (pinfunction "2_2") (pintype "passive"))
      (node (ref "C3") (pin "2") (pinfunction "2_2") (pintype "passive"))
      (node (ref "C30") (pin "-") (pinfunction "-_-") (pintype "passive"))
      (node (ref "C31") (pin "-") (pinfunction "-_-") (pintype "passive"))
      (node (ref "CON1") (pin "1") (pinfunction "GND1_1") (pintype "power_in"))
      (node (ref "CON1") (pin "10") (pinfunction "A09_10") (pintype "input"))
      (node (ref "CON1") (pin "11") (pinfunction "A08_11") (pintype "input"))
      (node (ref "CON1") (pin "12") (pinfunction "A07_12") (pintype "input"))
      (node (ref "CON1") (pin "14") (pinfunction "A06_14") (pintype "input"))
      (node (ref "CON1") (pin "15") (pinfunction "A05_15") (pintype "input"))
      (node (ref "CON1") (pin "16") (pinfunction "A04_16") (pintype "input"))
      (node (ref "CON1") (pin "17") (pinfunction "A03_17") (pintype "input"))
      (node (ref "CON1") (pin "39") (pinfunction "/CSEL_39") (pintype "input"))
      (node (ref "CON1") (pin "50") (pinfunction "GND2_50") (pintype "power_in"))
      (node (ref "CON1") (pin "8") (pinfunction "A10_8") (pintype "input"))
      (node (ref "CON1") (pin "9") (pinfunction "/ATASEL_9") (pintype "input"))
      (node (ref "D1") (pin "A") (pinfunction "A_A") (pintype "passive"))
      (node (ref "IC1") (pin "15") (pinfunction "GND_15") (pintype "power_in"))
      (node (ref "IC2") (pin "15") (pinfunction "GND_15") (pintype "power_in"))
      (node (ref "IC3") (pin "16") (pinfunction "GND_16") (pintype "power_in"))
      (node (ref "IC4") (pin "4") (pinfunction "G2A_4") (pintype "input"))
      (node (ref "IC4") (pin "8") (pinfunction "GND_8") (pintype "power_in"))
      (node (ref "IC5") (pin "3") (pinfunction "GND_3") (pintype "power_in"))
      (node (ref "IC5") (pin "5") (pinfunction "~{ON}/OFF_5") (pintype "input"))
      (node (ref "IC5") (pin "6") (pinfunction "THERM_6") (pintype "bidirectional"))
      (node (ref "IC6") (pin "10") (pinfunction "GND_10") (pintype "power_in"))
      (node (ref "IC6") (pin "13") (pinfunction "D5_13") (pintype "input"))
      (node (ref "IC6") (pin "14") (pinfunction "D6_14") (pintype "input"))
      (node (ref "IC6") (pin "17") (pinfunction "D7_17") (pintype "input"))
      (node (ref "IC6") (pin "18") (pinfunction "D8_18") (pintype "input"))
      (node (ref "IC7") (pin "3") (pinfunction "GND_3") (pintype "power_in"))
      (node (ref "IC9") (pin "1") (pinfunction "A_1") (pintype "input"))
      (node (ref "IC9") (pin "5") (pinfunction "G2B_5") (pintype "input"))
      (node (ref "IC9") (pin "8") (pinfunction "GND_8") (pintype "power_in"))
      (node (ref "JP5") (pin "1") (pinfunction "1_1") (pintype "passive"))
      (node (ref "JP7") (pin "2") (pinfunction "2_2") (pintype "passive"))
      (node (ref "LED1") (pin "C") (pinfunction "C_C") (pintype "passive"))
      (node (ref "R9") (pin "1") (pinfunction "1_1") (pintype "passive"))
      (node (ref "U$2") (pin "4") (pinfunction "GND_4") (pintype "bidirectional"))
      (node (ref "U$3") (pin "2") (pinfunction "GND_2") (pintype "power_in"))
      (node (ref "U$4") (pin "12") (pinfunction "VSS_12") (pintype "bidirectional"))
      (node (ref "U$4") (pin "34") (pinfunction "VSS_34") (pintype "bidirectional"))
      (node (ref "U$4") (pin "72") (pinfunction "VSS_72") (pintype "bidirectional"))
      (node (ref "U$4") (pin "73") (pinfunction "VSS_73") (pintype "bidirectional"))
      (node (ref "U1") (pin "16") (pinfunction "VSS_16") (pintype "output"))
      (node (ref "X1") (pin "5") (pinfunction "5_5") (pintype "passive"))
      (node (ref "X2") (pin "5") (pinfunction "5_5") (pintype "passive"))
    )
    (net (code "63") (name "LOCAL_PORT_CS") (class "Default")
      (node (ref "IC4") (pin "7") (pinfunction "Y7_7") (pintype "output"))
      (node (ref "IC7") (pin "1") (pinfunction "I0_1") (pintype "input"))
    )
    (net (code "64") (name "Net-(B1-PadAC1)") (class "Default")
      (node (ref "B1") (pin "AC1") (pinfunction "AC1_AC1") (pintype "passive"))
      (node (ref "F1") (pin "2") (pinfunction "2_2") (pintype "passive"))
    )
    (net (code "65") (name "Net-(CON1A-D07)") (class "Default")
      (node (ref "CON1") (pin "6") (pinfunction "D07_6") (pintype "bidirectional"))
      (node (ref "R2") (pin "1") (pinfunction "1_1") (pintype "passive"))
    )
    (net (code "66") (name "Net-(CON1A-{slash}CS1)") (class "Default")
      (node (ref "CON1") (pin "32") (pinfunction "/CS1_32") (pintype "input"))
      (node (ref "R12") (pin "1") (pinfunction "1_1") (pintype "passive"))
    )
    (net (code "67") (name "Net-(CON1A-{slash}DASP)") (class "Default")
      (node (ref "CON1") (pin "45") (pinfunction "/DASP_45") (pintype "bidirectional"))
      (node (ref "JP6") (pin "2") (pinfunction "2_2") (pintype "passive"))
    )
    (net (code "68") (name "Net-(CON1A-{slash}PDIAG)") (class "Default")
      (node (ref "CON1") (pin "46") (pinfunction "/PDIAG_46") (pintype "bidirectional"))
      (node (ref "R1") (pin "1") (pinfunction "1_1") (pintype "passive"))
    )
    (net (code "69") (name "Net-(CON1A-{slash}REG)") (class "Default")
      (node (ref "CON1") (pin "44") (pinfunction "/REG_44") (pintype "input"))
      (node (ref "R8") (pin "1") (pinfunction "1_1") (pintype "passive"))
    )
    (net (code "70") (name "Net-(CON1A-{slash}WE)") (class "Default")
      (node (ref "CON1") (pin "36") (pinfunction "/WE_36") (pintype "input"))
      (node (ref "R7") (pin "1") (pinfunction "1_1") (pintype "passive"))
    )
    (net (code "71") (name "Net-(F1-Pad1)") (class "Default")
      (node (ref "F1") (pin "1") (pinfunction "1_1") (pintype "passive"))
      (node (ref "JP8") (pin "2") (pinfunction "2_2") (pintype "passive"))
    )
    (net (code "72") (name "Net-(IC1A-C1+)") (class "Default")
      (node (ref "C4") (pin "2") (pinfunction "2_2") (pintype "passive"))
      (node (ref "IC1") (pin "1") (pinfunction "C1+_1") (pintype "bidirectional"))
    )
    (net (code "73") (name "Net-(IC1A-C1-)") (class "Default")
      (node (ref "C4") (pin "1") (pinfunction "1_1") (pintype "passive"))
      (node (ref "IC1") (pin "3") (pinfunction "C1-_3") (pintype "bidirectional"))
    )
    (net (code "74") (name "Net-(IC1A-C2+)") (class "Default")
      (node (ref "C5") (pin "2") (pinfunction "2_2") (pintype "passive"))
      (node (ref "IC1") (pin "4") (pinfunction "C2+_4") (pintype "bidirectional"))
    )
    (net (code "75") (name "Net-(IC1A-C2-)") (class "Default")
      (node (ref "C5") (pin "1") (pinfunction "1_1") (pintype "passive"))
      (node (ref "IC1") (pin "5") (pinfunction "C2-_5") (pintype "bidirectional"))
    )
    (net (code "76") (name "Net-(IC1A-R1IN)") (class "Default")
      (node (ref "IC1") (pin "13") (pinfunction "R1IN_13") (pintype "input"))
      (node (ref "X1") (pin "2") (pinfunction "2_2") (pintype "passive"))
    )
    (net (code "77") (name "Net-(IC1A-R2IN)") (class "Default")
      (node (ref "IC1") (pin "8") (pinfunction "R2IN_8") (pintype "input"))
      (node (ref "X1") (pin "8") (pinfunction "8_8") (pintype "passive"))
    )
    (net (code "78") (name "Net-(IC1A-T1OUT)") (class "Default")
      (node (ref "IC1") (pin "14") (pinfunction "T1OUT_14") (pintype "output"))
      (node (ref "X1") (pin "3") (pinfunction "3_3") (pintype "passive"))
    )
    (net (code "79") (name "Net-(IC1A-T2OUT)") (class "Default")
      (node (ref "IC1") (pin "7") (pinfunction "T2OUT_7") (pintype "output"))
      (node (ref "X1") (pin "7") (pinfunction "7_7") (pintype "passive"))
    )
    (net (code "80") (name "Net-(IC1A-V+)") (class "Default")
      (node (ref "C6") (pin "1") (pinfunction "1_1") (pintype "passive"))
      (node (ref "IC1") (pin "2") (pinfunction "V+_2") (pintype "bidirectional"))
    )
    (net (code "81") (name "Net-(IC1A-V-)") (class "Default")
      (node (ref "C25") (pin "1") (pinfunction "1_1") (pintype "passive"))
      (node (ref "IC1") (pin "6") (pinfunction "V-_6") (pintype "bidirectional"))
    )
    (net (code "82") (name "Net-(IC2A-C1+)") (class "Default")
      (node (ref "C7") (pin "2") (pinfunction "2_2") (pintype "passive"))
      (node (ref "IC2") (pin "1") (pinfunction "C1+_1") (pintype "bidirectional"))
    )
    (net (code "83") (name "Net-(IC2A-C1-)") (class "Default")
      (node (ref "C7") (pin "1") (pinfunction "1_1") (pintype "passive"))
      (node (ref "IC2") (pin "3") (pinfunction "C1-_3") (pintype "bidirectional"))
    )
    (net (code "84") (name "Net-(IC2A-C2+)") (class "Default")
      (node (ref "C8") (pin "2") (pinfunction "2_2") (pintype "passive"))
      (node (ref "IC2") (pin "4") (pinfunction "C2+_4") (pintype "bidirectional"))
    )
    (net (code "85") (name "Net-(IC2A-C2-)") (class "Default")
      (node (ref "C8") (pin "1") (pinfunction "1_1") (pintype "passive"))
      (node (ref "IC2") (pin "5") (pinfunction "C2-_5") (pintype "bidirectional"))
    )
    (net (code "86") (name "Net-(IC2A-R1IN)") (class "Default")
      (node (ref "IC2") (pin "13") (pinfunction "R1IN_13") (pintype "input"))
      (node (ref "X2") (pin "2") (pinfunction "2_2") (pintype "passive"))
    )
    (net (code "87") (name "Net-(IC2A-R2IN)") (class "Default")
      (node (ref "IC2") (pin "8") (pinfunction "R2IN_8") (pintype "input"))
      (node (ref "X2") (pin "8") (pinfunction "8_8") (pintype "passive"))
    )
    (net (code "88") (name "Net-(IC2A-T1OUT)") (class "Default")
      (node (ref "IC2") (pin "14") (pinfunction "T1OUT_14") (pintype "output"))
      (node (ref "X2") (pin "3") (pinfunction "3_3") (pintype "passive"))
    )
    (net (code "89") (name "Net-(IC2A-T2OUT)") (class "Default")
      (node (ref "IC2") (pin "7") (pinfunction "T2OUT_7") (pintype "output"))
      (node (ref "X2") (pin "7") (pinfunction "7_7") (pintype "passive"))
    )
    (net (code "90") (name "Net-(IC2A-V+)") (class "Default")
      (node (ref "C9") (pin "1") (pinfunction "1_1") (pintype "passive"))
      (node (ref "IC2") (pin "2") (pinfunction "V+_2") (pintype "bidirectional"))
    )
    (net (code "91") (name "Net-(IC2A-V-)") (class "Default")
      (node (ref "C10") (pin "1") (pinfunction "1_1") (pintype "passive"))
      (node (ref "IC2") (pin "6") (pinfunction "V-_6") (pintype "bidirectional"))
    )
    (net (code "92") (name "Net-(IC4A-G1)") (class "Default")
      (node (ref "IC4") (pin "6") (pinfunction "G1_6") (pintype "input"))
      (node (ref "R11") (pin "1") (pinfunction "1_1") (pintype "passive"))
    )
    (net (code "93") (name "Net-(IC5-OUT)") (class "Default")
      (node (ref "D1") (pin "C") (pinfunction "C_C") (pintype "passive"))
      (node (ref "IC5") (pin "2") (pinfunction "OUT_2") (pintype "output"))
      (node (ref "L2") (pin "P$1") (pinfunction "1_P$1") (pintype "passive"))
    )
    (net (code "94") (name "Net-(IC5-VIN)") (class "Default")
      (node (ref "B1") (pin "+") (pinfunction "+_+") (pintype "passive"))
      (node (ref "C21") (pin "+") (pinfunction "+_+") (pintype "passive"))
      (node (ref "C23") (pin "1") (pinfunction "1_1") (pintype "passive"))
      (node (ref "IC5") (pin "1") (pinfunction "VIN_1") (pintype "input"))
    )
    (net (code "95") (name "Net-(IC6A-CLK)") (class "Default")
      (node (ref "IC6") (pin "11") (pinfunction "CLK_11") (pintype "input"))
      (node (ref "IC7") (pin "4") (pinfunction "O_4") (pintype "output"))
    )
    (net (code "96") (name "Net-(IC6A-Q4)") (class "Default")
      (node (ref "IC6") (pin "9") (pinfunction "Q4_9") (pintype "output"))
      (node (ref "R17") (pin "2") (pinfunction "2_2") (pintype "passive"))
    )
    (net (code "97") (name "Net-(IC9A-C)") (class "Default")
      (node (ref "IC9") (pin "3") (pinfunction "C_3") (pintype "input"))
      (node (ref "R16") (pin "2") (pinfunction "2_2") (pintype "passive"))
    )
    (net (code "98") (name "Net-(IC9A-G1)") (class "Default")
      (node (ref "IC9") (pin "6") (pinfunction "G1_6") (pintype "input"))
      (node (ref "R18") (pin "1") (pinfunction "1_1") (pintype "passive"))
    )
    (net (code "99") (name "Net-(IC9A-Y2)") (class "Default")
      (node (ref "D2") (pin "C") (pinfunction "C_C") (pintype "passive"))
      (node (ref "IC9") (pin "13") (pinfunction "Y2_13") (pintype "output"))
    )
    (net (code "100") (name "Net-(IC9A-Y4)") (class "Default")
      (node (ref "D3") (pin "C") (pinfunction "C_C") (pintype "passive"))
      (node (ref "IC9") (pin "11") (pinfunction "Y4_11") (pintype "output"))
    )
    (net (code "101") (name "Net-(IC9A-Y6)") (class "Default")
      (node (ref "D4") (pin "C") (pinfunction "C_C") (pintype "passive"))
      (node (ref "IC9") (pin "9") (pinfunction "Y6_9") (pintype "output"))
    )
    (net (code "102") (name "Net-(J2-GND)") (class "Default")
      (node (ref "B1") (pin "AC2") (pinfunction "AC2_AC2") (pintype "passive"))
      (node (ref "J2") (pin "GND@1") (pinfunction "GNDBREAK_GND@1") (pintype "bidirectional"))
      (node (ref "J2") (pin "GND@2") (pinfunction "GND_GND@2") (pintype "bidirectional"))
    )
    (net (code "103") (name "Net-(J2-PadPWR)") (class "Default")
      (node (ref "J2") (pin "PWR") (pinfunction "PWR_PWR") (pintype "bidirectional"))
      (node (ref "JP8") (pin "1") (pinfunction "1_1") (pintype "passive"))
    )
    (net (code "104") (name "Net-(JP6-Pad1)") (class "Default")
      (node (ref "JP6") (pin "1") (pinfunction "1_1") (pintype "passive"))
      (node (ref "R13") (pin "1") (pinfunction "1_1") (pintype "passive"))
    )
    (net (code "105") (name "Net-(LED1-PadA)") (class "Default")
      (node (ref "LED1") (pin "A") (pinfunction "A_A") (pintype "passive"))
      (node (ref "R17") (pin "1") (pinfunction "1_1") (pintype "passive"))
    )
    (net (code "106") (name "Net-(U$2-CT)") (class "Default")
      (node (ref "C18") (pin "1") (pinfunction "1_1") (pintype "passive"))
      (node (ref "U$2") (pin "3") (pinfunction "CT_3") (pintype "bidirectional"))
    )
    (net (code "107") (name "Net-(U$2-REF)") (class "Default")
      (node (ref "C19") (pin "1") (pinfunction "1_1") (pintype "passive"))
      (node (ref "U$2") (pin "1") (pinfunction "REF_1") (pintype "bidirectional"))
    )
    (net (code "108") (name "Net-(U$2-RESET)") (class "Default")
      (node (ref "R9") (pin "2") (pinfunction "2_2") (pintype "passive"))
      (node (ref "U$2") (pin "6") (pinfunction "RESET_6") (pintype "bidirectional"))
    )
    (net (code "109") (name "Net-(U$2-~{RESIN})") (class "Default")
      (node (ref "JP5") (pin "2") (pinfunction "2_2") (pintype "passive"))
      (node (ref "R10") (pin "1") (pinfunction "1_1") (pintype "passive"))
      (node (ref "U$2") (pin "2") (pinfunction "~{RESIN}_2") (pintype "bidirectional"))
    )
    (net (code "110") (name "Net-(U$4-ST)") (class "Default")
      (node (ref "R14") (pin "1") (pinfunction "1_1") (pintype "passive"))
      (node (ref "U$4") (pin "7") (pinfunction "ST_7") (pintype "bidirectional"))
    )
    (net (code "111") (name "Net-(U$4-~{DREQ1})") (class "Default")
      (node (ref "R15") (pin "1") (pinfunction "1_1") (pintype "passive"))
      (node (ref "U$4") (pin "59") (pinfunction "~{DREQ1}_59") (pintype "bidirectional"))
    )
    (net (code "124") (name "ROMSHADOW") (class "Default")
      (node (ref "IC6") (pin "6") (pinfunction "Q3_6") (pintype "output"))
      (node (ref "IC9") (pin "2") (pinfunction "B_2") (pintype "input"))
    )
    (net (code "125") (name "RTS1") (class "Default")
      (node (ref "IC2") (pin "10") (pinfunction "T2IN_10") (pintype "input"))
      (node (ref "U$4") (pin "45") (pinfunction "~{RTS0}_45") (pintype "bidirectional"))
    )
    (net (code "126") (name "RTS2") (class "Default")
      (node (ref "IC1") (pin "10") (pinfunction "T2IN_10") (pintype "input"))
      (node (ref "IC6") (pin "2") (pinfunction "Q1_2") (pintype "output"))
    )
    (net (code "127") (name "RX") (class "Default")
      (node (ref "JP11") (pin "1") (pinfunction "1_1") (pintype "passive"))
    )
    (net (code "128") (name "RXD1") (class "Default")
      (node (ref "IC2") (pin "12") (pinfunction "R1OUT_12") (pintype "output"))
      (node (ref "U$4") (pin "49") (pinfunction "RXA0_49") (pintype "bidirectional"))
    )
    (net (code "129") (name "RXD2") (class "Default")
      (node (ref "IC1") (pin "12") (pinfunction "R1OUT_12") (pintype "output"))
      (node (ref "U$4") (pin "54") (pinfunction "RXA1_54") (pintype "bidirectional"))
    )
    (net (code "131") (name "TX") (class "Default")
      (node (ref "JP11") (pin "2") (pinfunction "2_2") (pintype "passive"))
    )
    (net (code "132") (name "TXD1") (class "Default")
      (node (ref "IC2") (pin "11") (pinfunction "T1IN_11") (pintype "input"))
      (node (ref "U$4") (pin "48") (pinfunction "TXA0_48") (pintype "bidirectional"))
    )
    (net (code "133") (name "TXD2") (class "Default")
      (node (ref "IC1") (pin "11") (pinfunction "T1IN_11") (pintype "input"))
      (node (ref "U$4") (pin "52") (pinfunction "TXA1_52") (pintype "bidirectional"))
    )
    (net (code "134") (name "XTAL") (class "Default")
      (node (ref "U$4") (pin "74") (pinfunction "XTAL_74") (pintype "bidirectional"))
    )
    (net (code "135") (name "unconnected-(CON1A-D08-Pad47)") (class "Default")
      (node (ref "CON1") (pin "47") (pinfunction "D08_47") (pintype "bidirectional"))
    )
    (net (code "136") (name "unconnected-(CON1A-D09-Pad48)") (class "Default")
      (node (ref "CON1") (pin "48") (pinfunction "D09_48") (pintype "bidirectional"))
    )
    (net (code "137") (name "unconnected-(CON1A-D10-Pad49)") (class "Default")
      (node (ref "CON1") (pin "49") (pinfunction "D10_49") (pintype "bidirectional"))
    )
    (net (code "138") (name "unconnected-(CON1A-D11-Pad27)") (class "Default")
      (node (ref "CON1") (pin "27") (pinfunction "D11_27") (pintype "bidirectional"))
    )
    (net (code "139") (name "unconnected-(CON1A-D12-Pad28)") (class "Default")
      (node (ref "CON1") (pin "28") (pinfunction "D12_28") (pintype "bidirectional"))
    )
    (net (code "140") (name "unconnected-(CON1A-D13-Pad29)") (class "Default")
      (node (ref "CON1") (pin "29") (pinfunction "D13_29") (pintype "bidirectional"))
    )
    (net (code "141") (name "unconnected-(CON1A-D14-Pad30)") (class "Default")
      (node (ref "CON1") (pin "30") (pinfunction "D14_30") (pintype "bidirectional"))
    )
    (net (code "142") (name "unconnected-(CON1A-D15-Pad31)") (class "Default")
      (node (ref "CON1") (pin "31") (pinfunction "D15_31") (pintype "bidirectional"))
    )
    (net (code "143") (name "unconnected-(CON1A-INTRQ-Pad37)") (class "Default")
      (node (ref "CON1") (pin "37") (pinfunction "INTRQ_37") (pintype "output"))
    )
    (net (code "144") (name "unconnected-(CON1A-IORDY-Pad42)") (class "Default")
      (node (ref "CON1") (pin "42") (pinfunction "IORDY_42") (pintype "output"))
    )
    (net (code "145") (name "unconnected-(CON1A-{slash}CD1-Pad26)") (class "Default")
      (node (ref "CON1") (pin "26") (pinfunction "/CD1_26") (pintype "output"))
    )
    (net (code "146") (name "unconnected-(CON1A-{slash}CD2-Pad25)") (class "Default")
      (node (ref "CON1") (pin "25") (pinfunction "/CD2_25") (pintype "output"))
    )
    (net (code "147") (name "unconnected-(CON1A-{slash}INPACK-Pad43)") (class "Default")
      (node (ref "CON1") (pin "43") (pinfunction "/INPACK_43") (pintype "output"))
    )
    (net (code "148") (name "unconnected-(CON1A-{slash}IOCS16-Pad24)") (class "Default")
      (node (ref "CON1") (pin "24") (pinfunction "/IOCS16_24") (pintype "output"))
    )
    (net (code "149") (name "unconnected-(CON1A-{slash}VS1-Pad33)") (class "Default")
      (node (ref "CON1") (pin "33") (pinfunction "/VS1_33") (pintype "output"))
    )
    (net (code "150") (name "unconnected-(CON1A-{slash}VS2-Pad40)") (class "Default")
      (node (ref "CON1") (pin "40") (pinfunction "/VS2_40") (pintype "output"))
    )
    (net (code "151") (name "unconnected-(IC6A-Q2-Pad5)") (class "Default")
      (node (ref "IC6") (pin "5") (pinfunction "Q2_5") (pintype "output"))
    )
    (net (code "152") (name "unconnected-(IC6A-Q5-Pad12)") (class "Default")
      (node (ref "IC6") (pin "12") (pinfunction "Q5_12") (pintype "output"))
    )
    (net (code "153") (name "unconnected-(IC6A-Q6-Pad15)") (class "Default")
      (node (ref "IC6") (pin "15") (pinfunction "Q6_15") (pintype "output"))
    )
    (net (code "154") (name "unconnected-(IC6A-Q7-Pad16)") (class "Default")
      (node (ref "IC6") (pin "16") (pinfunction "Q7_16") (pintype "output"))
    )
    (net (code "155") (name "unconnected-(IC6A-Q8-Pad19)") (class "Default")
      (node (ref "IC6") (pin "19") (pinfunction "Q8_19") (pintype "output"))
    )
    (net (code "156") (name "unconnected-(IC9A-Y1-Pad14)") (class "Default")
      (node (ref "IC9") (pin "14") (pinfunction "Y1_14") (pintype "output"))
    )
    (net (code "157") (name "unconnected-(IC9A-Y3-Pad12)") (class "Default")
      (node (ref "IC9") (pin "12") (pinfunction "Y3_12") (pintype "output"))
    )
    (net (code "158") (name "unconnected-(IC9A-Y5-Pad10)") (class "Default")
      (node (ref "IC9") (pin "10") (pinfunction "Y5_10") (pintype "output"))
    )
    (net (code "159") (name "unconnected-(IC9A-Y7-Pad7)") (class "Default")
      (node (ref "IC9") (pin "7") (pinfunction "Y7_7") (pintype "output"))
    )
    (net (code "160") (name "unconnected-(JP2-Pad8)") (class "Default")
      (node (ref "JP2") (pin "8") (pinfunction "8_8") (pintype "passive"))
    )
    (net (code "161") (name "unconnected-(U$3-TRI-Pad1)") (class "Default")
      (node (ref "U$3") (pin "1") (pinfunction "TRI_1") (pintype "input"))
    )
    (net (code "162") (name "unconnected-(U$4-A19-Pad33)") (class "Default")
      (node (ref "U$4") (pin "33") (pinfunction "A19_33") (pintype "bidirectional"))
    )
    (net (code "163") (name "unconnected-(U$4-CKA0{slash}~{DREQ0}-Pad50)") (class "Default")
      (node (ref "U$4") (pin "50") (pinfunction "CKA0/~{DREQ0}_50") (pintype "bidirectional"))
    )
    (net (code "164") (name "unconnected-(U$4-CKA1{slash}~{TEND0}-Pad55)") (class "Default")
      (node (ref "U$4") (pin "55") (pinfunction "CKA1/~{TEND0}_55") (pintype "bidirectional"))
    )
    (net (code "165") (name "unconnected-(U$4-CKS-Pad58)") (class "Default")
      (node (ref "U$4") (pin "58") (pinfunction "CKS_58") (pintype "bidirectional"))
    )
    (net (code "166") (name "unconnected-(U$4-NC-Pad2)") (class "Default")
      (node (ref "U$4") (pin "2") (pinfunction "NC_2") (pintype "bidirectional"))
    )
    (net (code "167") (name "unconnected-(U$4-NC-Pad3)") (class "Default")
      (node (ref "U$4") (pin "3") (pinfunction "NC_3") (pintype "bidirectional"))
    )
    (net (code "168") (name "unconnected-(U$4-NC-Pad14)") (class "Default")
      (node (ref "U$4") (pin "14") (pinfunction "NC_14") (pintype "bidirectional"))
    )
    (net (code "169") (name "unconnected-(U$4-NC-Pad22)") (class "Default")
      (node (ref "U$4") (pin "22") (pinfunction "NC_22") (pintype "bidirectional"))
    )
    (net (code "170") (name "unconnected-(U$4-NC-Pad23)") (class "Default")
      (node (ref "U$4") (pin "23") (pinfunction "NC_23") (pintype "bidirectional"))
    )
    (net (code "171") (name "unconnected-(U$4-NC-Pad30)") (class "Default")
      (node (ref "U$4") (pin "30") (pinfunction "NC_30") (pintype "bidirectional"))
    )
    (net (code "172") (name "unconnected-(U$4-NC-Pad42)") (class "Default")
      (node (ref "U$4") (pin "42") (pinfunction "NC_42") (pintype "bidirectional"))
    )
    (net (code "173") (name "unconnected-(U$4-NC-Pad43)") (class "Default")
      (node (ref "U$4") (pin "43") (pinfunction "NC_43") (pintype "bidirectional"))
    )
    (net (code "174") (name "unconnected-(U$4-NC-Pad51)") (class "Default")
      (node (ref "U$4") (pin "51") (pinfunction "NC_51") (pintype "bidirectional"))
    )
    (net (code "175") (name "unconnected-(U$4-NC-Pad53)") (class "Default")
      (node (ref "U$4") (pin "53") (pinfunction "NC_53") (pintype "bidirectional"))
    )
    (net (code "176") (name "unconnected-(U$4-NC-Pad62)") (class "Default")
      (node (ref "U$4") (pin "62") (pinfunction "NC_62") (pintype "bidirectional"))
    )
    (net (code "177") (name "unconnected-(U$4-NC-Pad63)") (class "Default")
      (node (ref "U$4") (pin "63") (pinfunction "NC_63") (pintype "bidirectional"))
    )
    (net (code "178") (name "unconnected-(U$4-NC-Pad75)") (class "Default")
      (node (ref "U$4") (pin "75") (pinfunction "NC_75") (pintype "bidirectional"))
    )
    (net (code "179") (name "unconnected-(U$4-TXS-Pad56)") (class "Default")
      (node (ref "U$4") (pin "56") (pinfunction "TXS_56") (pintype "bidirectional"))
    )
    (net (code "180") (name "unconnected-(U$4-~{DCD0}-Pad47)") (class "Default")
      (node (ref "U$4") (pin "47") (pinfunction "~{DCD0}_47") (pintype "bidirectional"))
    )
    (net (code "181") (name "unconnected-(U$4-~{HALT}-Pad61)") (class "Default")
      (node (ref "U$4") (pin "61") (pinfunction "~{HALT}_61") (pintype "bidirectional"))
    )
    (net (code "182") (name "unconnected-(U$4-~{LIR}-Pad68)") (class "Default")
      (node (ref "U$4") (pin "68") (pinfunction "~{LIR}_68") (pintype "bidirectional"))
    )
    (net (code "183") (name "unconnected-(U$4-~{REF}-Pad64)") (class "Default")
      (node (ref "U$4") (pin "64") (pinfunction "~{REF}_64") (pintype "bidirectional"))
    )
    (net (code "184") (name "unconnected-(U$4-~{TEND1}-Pad60)") (class "Default")
      (node (ref "U$4") (pin "60") (pinfunction "~{TEND1}_60") (pintype "bidirectional"))
    )
    (net (code "185") (name "unconnected-(X1-Pad1)") (class "Default")
      (node (ref "X1") (pin "1") (pinfunction "1_1") (pintype "passive"))
    )
    (net (code "186") (name "unconnected-(X1-Pad4)") (class "Default")
      (node (ref "X1") (pin "4") (pinfunction "4_4") (pintype "passive"))
    )
    (net (code "187") (name "unconnected-(X1-Pad6)") (class "Default")
      (node (ref "X1") (pin "6") (pinfunction "6_6") (pintype "passive"))
    )
    (net (code "188") (name "unconnected-(X1-Pad9)") (class "Default")
      (node (ref "X1") (pin "9") (pinfunction "9_9") (pintype "passive"))
    )
    (net (code "189") (name "unconnected-(X2-Pad1)") (class "Default")
      (node (ref "X2") (pin "1") (pinfunction "1_1") (pintype "passive"))
    )
    (net (code "190") (name "unconnected-(X2-Pad4)") (class "Default")
      (node (ref "X2") (pin "4") (pinfunction "4_4") (pintype "passive"))
    )
    (net (code "191") (name "unconnected-(X2-Pad6)") (class "Default")
      (node (ref "X2") (pin "6") (pinfunction "6_6") (pintype "passive"))
    )
    (net (code "192") (name "unconnected-(X2-Pad9)") (class "Default")
      (node (ref "X2") (pin "9") (pinfunction "9_9") (pintype "passive"))
    )
  )
)
